# main.net
KiCad netlist of a schematic drawn in Altium Designer
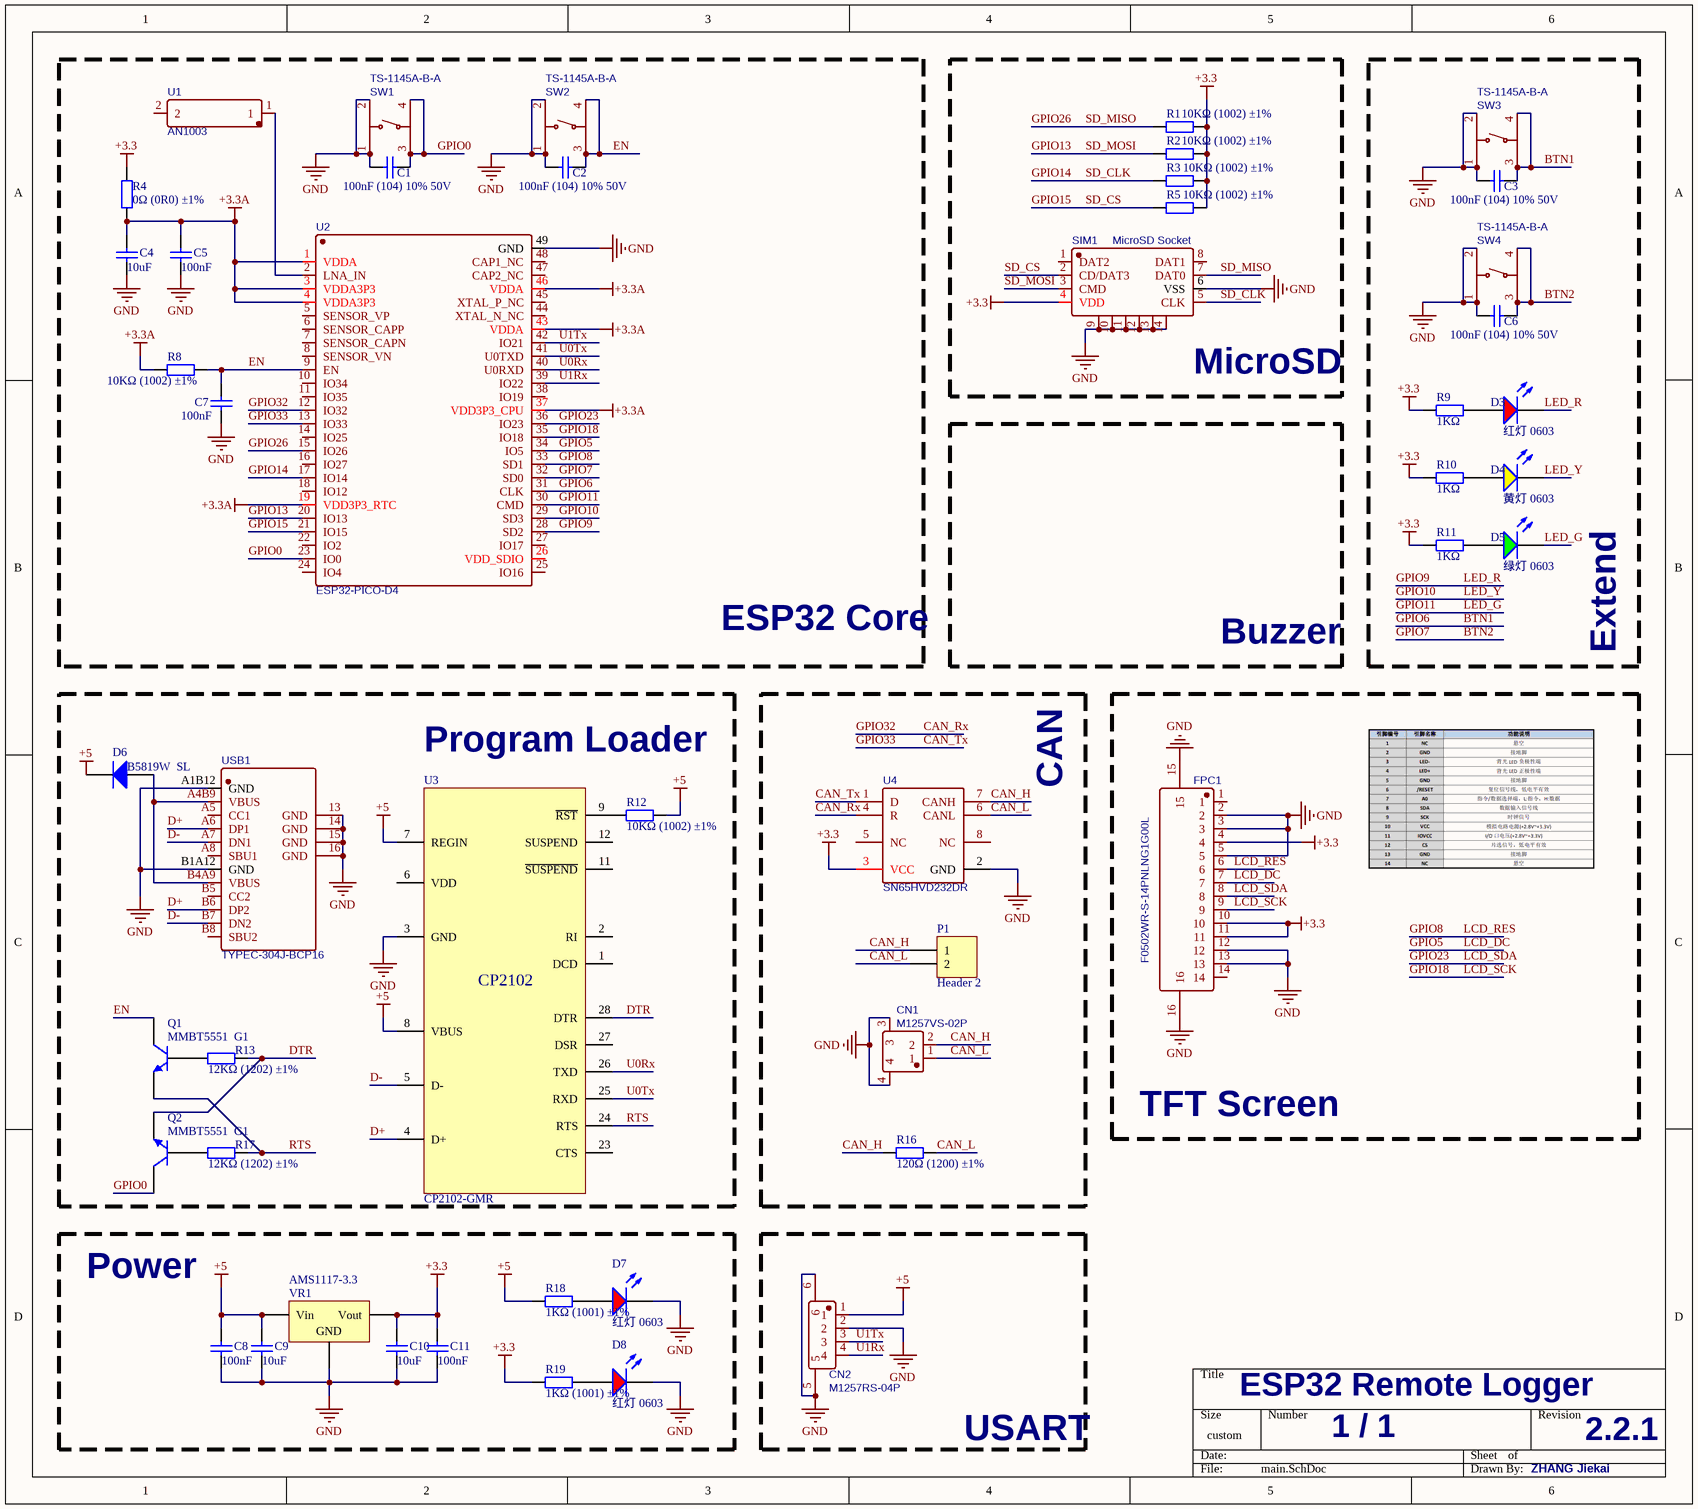
[diagram p0: main.SchDoc]

(export (version "E")
  (design (tool "Eeschema 10.0.6"))
  (components
    (comp (ref "C1")
      (value "100nF (104) 10% 50V")
      (footprint "0603_C")
      (description "贴片电容")
      (libsource (lib "Miscellaneous Devices LC") (part "0603 100nF (104) 10% 50V"))
    )
    (comp (ref "C2")
      (value "100nF (104) 10% 50V")
      (footprint "0603_C")
      (description "贴片电容")
      (libsource (lib "Miscellaneous Devices LC") (part "0603 100nF (104) 10% 50V"))
    )
    (comp (ref "C3")
      (value "100nF (104) 10% 50V")
      (footprint "0603_C")
      (description "贴片电容")
      (libsource (lib "Miscellaneous Devices LC") (part "0603 100nF (104) 10% 50V"))
    )
    (comp (ref "C4")
      (value "10uF")
      (footprint "0603_C")
      (description "贴片电容")
      (libsource (lib "Miscellaneous Devices LC") (part "0603 10uF (106) 10% 10V"))
    )
    (comp (ref "C5")
      (value "100nF")
      (footprint "0603_C")
      (description "贴片电容")
      (libsource (lib "Miscellaneous Devices LC") (part "0603 100nF (104) 10% 50V"))
    )
    (comp (ref "C6")
      (value "100nF (104) 10% 50V")
      (footprint "0603_C")
      (description "贴片电容")
      (libsource (lib "Miscellaneous Devices LC") (part "0603 100nF (104) 10% 50V"))
    )
    (comp (ref "C7")
      (value "100nF")
      (footprint "0603_C")
      (description "贴片电容")
      (libsource (lib "Miscellaneous Devices LC") (part "0603 100nF (104) 10% 50V"))
    )
    (comp (ref "C8")
      (value "100nF")
      (footprint "0603_C")
      (description "贴片电容")
      (libsource (lib "Miscellaneous Devices LC") (part "0603 100nF (104) 10% 50V"))
    )
    (comp (ref "C9")
      (value "10uF")
      (footprint "0603_C")
      (description "贴片电容")
      (libsource (lib "Miscellaneous Devices LC") (part "0603 10uF (106) 10% 10V"))
    )
    (comp (ref "C10")
      (value "10uF")
      (footprint "0603_C")
      (description "贴片电容")
      (libsource (lib "Miscellaneous Devices LC") (part "0603 10uF (106) 10% 10V"))
    )
    (comp (ref "C11")
      (value "100nF")
      (footprint "0603_C")
      (description "贴片电容")
      (libsource (lib "Miscellaneous Devices LC") (part "0603 100nF (104) 10% 50V"))
    )
    (comp (ref "CN1")
      (value "M1257VS-02P")
      (footprint "CONN-SMD_P1.25_M1257VS-02P")
      (fields (field (name "BOM_SUPPLIER PART") "C541819") (field (name "CONTRIBUTOR") "LCSC"))
      (libsource (lib "GH2P_Stand") (part "M1257VS-02P"))
    )
    (comp (ref "CN2")
      (value "M1257RS-04P")
      (footprint "CONN-SMD_M1257RS-04P")
      (fields (field (name "BOM_SUPPLIER PART") "C541828") (field (name "CONTRIBUTOR") "LCSC"))
      (libsource (lib "GH-lay-4P") (part "M1257RS-04P"))
    )
    (comp (ref "D3")
      (value "红灯 0603")
      (footprint "0603_LED_S1")
      (description "发光二极管")
      (libsource (lib "Miscellaneous Devices LC") (part "0603 红灯"))
    )
    (comp (ref "D4")
      (value "黄灯 0603")
      (footprint "0603_LED_S1")
      (description "发光二极管")
      (libsource (lib "Miscellaneous Devices LC") (part "0603 黄灯"))
    )
    (comp (ref "D5")
      (value "绿灯 0603")
      (footprint "0603_LED_S1")
      (description "发光二极管")
      (libsource (lib "Miscellaneous Devices LC") (part "0603 绿灯"))
    )
    (comp (ref "D6")
      (value "B5819W  SL")
      (footprint "SOD-123")
      (description "肖特基二极管")
      (libsource (lib "Miscellaneous Devices LC") (part "SOD-123 B5819W  SL"))
    )
    (comp (ref "D7")
      (value "红灯 0603")
      (footprint "0603_LED_S1")
      (description "发光二极管")
      (libsource (lib "Miscellaneous Devices LC") (part "0603 红灯"))
    )
    (comp (ref "D8")
      (value "红灯 0603")
      (footprint "0603_LED_S1")
      (description "发光二极管")
      (libsource (lib "Miscellaneous Devices LC") (part "0603 红灯"))
    )
    (comp (ref "FPC1")
      (value "F0502WR-S-14PNLNG1G00L")
      (footprint "FPC-SMD_P0.50-14P_F0500WR-S")
      (fields (field (name "BOM_SUPPLIER PART") "C247902") (field (name "CONTRIBUTOR") "LCSC"))
      (libsource (lib "14P-FFC-Connector") (part "F0502WR-S-14PNLNG1G00L"))
    )
    (comp (ref "P1")
      (value "Header 2")
      (footprint "HDR1X2")
      (description "Header, 2-Pin")
      (fields (field (name "PUBLISHER") "Altium Limited"))
      (libsource (lib "Miscellaneous Connectors") (part "Header 2"))
    )
    (comp (ref "Q1")
      (value "MMBT5551  G1")
      (footprint "SOT-23(SOT-23-3)")
      (description "三极管")
      (libsource (lib "Miscellaneous Devices LC") (part "SOT-23 MMBT5551  G1"))
    )
    (comp (ref "Q2")
      (value "MMBT5551  G1")
      (footprint "SOT-23(SOT-23-3)")
      (description "三极管")
      (libsource (lib "Miscellaneous Devices LC") (part "SOT-23 MMBT5551  G1"))
    )
    (comp (ref "R1")
      (value "10KΩ (1002) ±1%")
      (footprint "0603_R")
      (description "贴片电阻")
      (libsource (lib "Miscellaneous Devices LC") (part "0603 10KΩ (1002) 1%"))
    )
    (comp (ref "R2")
      (value "10KΩ (1002) ±1%")
      (footprint "0603_R")
      (description "贴片电阻")
      (libsource (lib "Miscellaneous Devices LC") (part "0603 10KΩ (1002) 1%"))
    )
    (comp (ref "R3")
      (value "10KΩ (1002) ±1%")
      (footprint "0603_R")
      (description "贴片电阻")
      (libsource (lib "Miscellaneous Devices LC") (part "0603 10KΩ (1002) 1%"))
    )
    (comp (ref "R4")
      (value "0Ω (0R0) ±1%")
      (footprint "0603_R")
      (description "贴片电阻")
      (libsource (lib "Miscellaneous Devices LC") (part "0603 0Ω (0R0) 1%"))
    )
    (comp (ref "R5")
      (value "10KΩ (1002) ±1%")
      (footprint "0603_R")
      (description "贴片电阻")
      (libsource (lib "Miscellaneous Devices LC") (part "0603 10KΩ (1002) 1%"))
    )
    (comp (ref "R8")
      (value "10KΩ (1002) ±1%")
      (footprint "0603_R")
      (description "贴片电阻")
      (libsource (lib "Miscellaneous Devices LC") (part "0603 10KΩ (1002) 1%"))
    )
    (comp (ref "R9")
      (value "1KΩ")
      (footprint "0603_R")
      (description "贴片电阻")
      (libsource (lib "") (part "0603 1KΩ (1001) 1%_1"))
    )
    (comp (ref "R10")
      (value "1KΩ")
      (footprint "0603_R")
      (description "贴片电阻")
      (libsource (lib "") (part "0603 1KΩ (1001) 1%_1"))
    )
    (comp (ref "R11")
      (value "1KΩ")
      (footprint "0603_R")
      (description "贴片电阻")
      (libsource (lib "") (part "0603 1KΩ (1001) 1%_1"))
    )
    (comp (ref "R12")
      (value "10KΩ (1002) ±1%")
      (footprint "0603_R")
      (description "贴片电阻")
      (libsource (lib "Miscellaneous Devices LC") (part "0603 10KΩ (1002) 1%"))
    )
    (comp (ref "R13")
      (value "12KΩ (1202) ±1%")
      (footprint "0603_R")
      (description "贴片电阻")
      (libsource (lib "Miscellaneous Devices LC") (part "0603 12KΩ (1202) 1%"))
    )
    (comp (ref "R16")
      (value "120Ω (1200) ±1%")
      (footprint "0603_R")
      (description "贴片电阻")
      (libsource (lib "Miscellaneous Devices LC") (part "0603 120Ω (1200) 1%"))
    )
    (comp (ref "R17")
      (value "12KΩ (1202) ±1%")
      (footprint "0603_R")
      (description "贴片电阻")
      (libsource (lib "Miscellaneous Devices LC") (part "0603 12KΩ (1202) 1%"))
    )
    (comp (ref "R18")
      (value "1KΩ (1001) ±1%")
      (footprint "0603_R")
      (description "贴片电阻")
      (libsource (lib "Miscellaneous Devices LC") (part "0603 1KΩ (1001) 1%"))
    )
    (comp (ref "R19")
      (value "1KΩ (1001) ±1%")
      (footprint "0603_R")
      (description "贴片电阻")
      (libsource (lib "Miscellaneous Devices LC") (part "0603 1KΩ (1001) 1%"))
    )
    (comp (ref "SIM1")
      (value "MicroSD Socket")
      (footprint "SIM-SMD_8P-1040310811")
      (fields
        (field (name "BOM_SUPPLIER PART") "C585350")
        (field (name "BOM_MANUFACTURER PART") "1040310811")
        (field (name "CONTRIBUTOR") "LCSC")
      )
      (libsource (lib "MicroSD-Socket") (part "1040310811"))
    )
    (comp (ref "SW1")
      (value "TS-1145A-B-A")
      (footprint "SW-SMD_4P-L4.2-W3.2-P2.15-LS5.2")
      (fields (field (name "BOM_SUPPLIER PART") "C318904") (field (name "CONTRIBUTOR") "LCSC"))
      (libsource (lib "Pad-Button") (part "TS-1145A-B-A"))
    )
    (comp (ref "SW2")
      (value "TS-1145A-B-A")
      (footprint "SW-SMD_4P-L4.2-W3.2-P2.15-LS5.2")
      (fields (field (name "BOM_SUPPLIER PART") "C318904") (field (name "CONTRIBUTOR") "LCSC"))
      (libsource (lib "Pad-Button") (part "TS-1145A-B-A"))
    )
    (comp (ref "SW3")
      (value "TS-1145A-B-A")
      (footprint "SW-SMD_4P-L4.2-W3.2-P2.15-LS5.2")
      (fields (field (name "BOM_SUPPLIER PART") "C318904") (field (name "CONTRIBUTOR") "LCSC"))
      (libsource (lib "Pad-Button") (part "TS-1145A-B-A"))
    )
    (comp (ref "SW4")
      (value "TS-1145A-B-A")
      (footprint "SW-SMD_4P-L4.2-W3.2-P2.15-LS5.2")
      (fields (field (name "BOM_SUPPLIER PART") "C318904") (field (name "CONTRIBUTOR") "LCSC"))
      (libsource (lib "Pad-Button") (part "TS-1145A-B-A"))
    )
    (comp (ref "U1")
      (value "AN1003")
      (footprint "ANT-SMD_L10.3-W3.0")
      (fields (field (name "BOM_SUPPLIER PART") "C239240") (field (name "CONTRIBUTOR") "LCSC"))
      (libsource (lib "AN1003") (part "AN1003"))
    )
    (comp (ref "U2")
      (value "ESP32-PICO-D4")
      (footprint "QFN-48_L7.0-W7.0-P0.50-BL-EP5.4")
      (fields (field (name "BOM_SUPPLIER PART") "C193707") (field (name "CONTRIBUTOR") "LCSC"))
      (libsource (lib "ESP32-PICO-D4") (part "ESP32-PICO-D4"))
    )
    (comp (ref "U3")
      (value "CP2102-GMR")
      (footprint "QFN-28_5x5x05P")
      (description "USB")
      (libsource (lib "Miscellaneous Devices LC") (part "CP2102-GMR_[C6568]"))
    )
    (comp (ref "U4")
      (value "SN65HVD232DR")
      (footprint "SOIC-8_L5.0-W4.0-P1.27-LS6.0-BL")
      (fields (field (name "BOM_SUPPLIER PART") "C30530"))
      (libsource (lib "SN65HVD232DR") (part "SN65HVD232DR"))
    )
    (comp (ref "USB1")
      (value "TYPEC-304J-BCP16")
      (footprint "USB-C-SMD_TYPEC-304J-BCP16")
      (fields (field (name "BOM_SUPPLIER PART") "C2835315") (field (name "CONTRIBUTOR") "LCSC"))
      (libsource (lib "Pad-Typec") (part "TYPEC-304J-BCP16"))
    )
    (comp (ref "VR1")
      (value "AMS1117-3.3")
      (footprint "SOT-223")
      (description "低压差线性稳压(LDO)")
      (libsource (lib "Miscellaneous Devices LC") (part "SOT-223 AMS1117-3.3"))
    )
  )
  (nets
    (net (code "1") (name "+3.3") (class "Default")
      (node (ref "C10") (pin "2") (pinfunction "2_2") (pintype "passive"))
      (node (ref "C11") (pin "2") (pinfunction "2_2") (pintype "passive"))
      (node (ref "FPC1") (pin "10") (pinfunction "10_10") (pintype "passive"))
      (node (ref "FPC1") (pin "11") (pinfunction "11_11") (pintype "passive"))
      (node (ref "FPC1") (pin "4") (pinfunction "4_4") (pintype "passive"))
      (node (ref "R1") (pin "2") (pinfunction "2_2") (pintype "passive"))
      (node (ref "R10") (pin "2") (pinfunction "2_2") (pintype "passive"))
      (node (ref "R11") (pin "2") (pinfunction "2_2") (pintype "passive"))
      (node (ref "R19") (pin "1") (pinfunction "1_1") (pintype "passive"))
      (node (ref "R2") (pin "2") (pinfunction "2_2") (pintype "passive"))
      (node (ref "R3") (pin "2") (pinfunction "2_2") (pintype "passive"))
      (node (ref "R4") (pin "2") (pinfunction "2_2") (pintype "passive"))
      (node (ref "R5") (pin "2") (pinfunction "2_2") (pintype "passive"))
      (node (ref "R9") (pin "2") (pinfunction "2_2") (pintype "passive"))
      (node (ref "SIM1") (pin "4") (pinfunction "VDD_4") (pintype "passive"))
      (node (ref "U4") (pin "3") (pinfunction "VCC_3") (pintype "passive"))
      (node (ref "VR1") (pin "2") (pinfunction "Vout_2") (pintype "passive"))
    )
    (net (code "2") (name "+3.3A") (class "Default")
      (node (ref "C4") (pin "2") (pinfunction "2_2") (pintype "passive"))
      (node (ref "C5") (pin "2") (pinfunction "2_2") (pintype "passive"))
      (node (ref "R4") (pin "1") (pinfunction "1_1") (pintype "passive"))
      (node (ref "R8") (pin "1") (pinfunction "1_1") (pintype "passive"))
      (node (ref "U2") (pin "1") (pinfunction "VDDA_1") (pintype "passive"))
      (node (ref "U2") (pin "19") (pinfunction "VDD3P3_RTC_19") (pintype "passive"))
      (node (ref "U2") (pin "3") (pinfunction "VDDA3P3_3") (pintype "passive"))
      (node (ref "U2") (pin "37") (pinfunction "VDD3P3_CPU_37") (pintype "passive"))
      (node (ref "U2") (pin "4") (pinfunction "VDDA3P3_4") (pintype "passive"))
      (node (ref "U2") (pin "43") (pinfunction "VDDA_43") (pintype "passive"))
      (node (ref "U2") (pin "46") (pinfunction "VDDA_46") (pintype "passive"))
    )
    (net (code "3") (name "+5") (class "Default")
      (node (ref "C8") (pin "2") (pinfunction "2_2") (pintype "passive"))
      (node (ref "C9") (pin "2") (pinfunction "2_2") (pintype "passive"))
      (node (ref "CN2") (pin "1") (pinfunction "1_1") (pintype "passive"))
      (node (ref "D6") (pin "2") (pinfunction "K_2") (pintype "passive"))
      (node (ref "R12") (pin "2") (pinfunction "2_2") (pintype "passive"))
      (node (ref "R18") (pin "1") (pinfunction "1_1") (pintype "passive"))
      (node (ref "U3") (pin "7") (pinfunction "REGIN_7") (pintype "passive"))
      (node (ref "U3") (pin "8") (pinfunction "VBUS_8") (pintype "passive"))
      (node (ref "VR1") (pin "3") (pinfunction "Vin_3") (pintype "passive"))
    )
    (net (code "4") (name "/BTN1") (class "Default")
      (node (ref "C3") (pin "2") (pinfunction "2_2") (pintype "passive"))
      (node (ref "SW3") (pin "3") (pinfunction "3_3") (pintype "passive"))
      (node (ref "SW3") (pin "4") (pinfunction "4_4") (pintype "passive"))
      (node (ref "U2") (pin "31") (pinfunction "CLK_31") (pintype "passive"))
    )
    (net (code "5") (name "/BTN2") (class "Default")
      (node (ref "C6") (pin "2") (pinfunction "2_2") (pintype "passive"))
      (node (ref "SW4") (pin "3") (pinfunction "3_3") (pintype "passive"))
      (node (ref "SW4") (pin "4") (pinfunction "4_4") (pintype "passive"))
      (node (ref "U2") (pin "32") (pinfunction "SD0_32") (pintype "passive"))
    )
    (net (code "6") (name "/CAN_H") (class "Default")
      (node (ref "CN1") (pin "2") (pinfunction "2_2") (pintype "passive"))
      (node (ref "P1") (pin "1") (pinfunction "1_1") (pintype "passive"))
      (node (ref "R16") (pin "1") (pinfunction "1_1") (pintype "passive"))
      (node (ref "U4") (pin "7") (pinfunction "CANH_7") (pintype "passive"))
    )
    (net (code "7") (name "/CAN_L") (class "Default")
      (node (ref "CN1") (pin "1") (pinfunction "1_1") (pintype "passive"))
      (node (ref "P1") (pin "2") (pinfunction "2_2") (pintype "passive"))
      (node (ref "R16") (pin "2") (pinfunction "2_2") (pintype "passive"))
      (node (ref "U4") (pin "6") (pinfunction "CANL_6") (pintype "passive"))
    )
    (net (code "8") (name "/CAN_Rx") (class "Default")
      (node (ref "U2") (pin "12") (pinfunction "IO32_12") (pintype "passive"))
      (node (ref "U4") (pin "4") (pinfunction "R_4") (pintype "passive"))
    )
    (net (code "9") (name "/CAN_Tx") (class "Default")
      (node (ref "U2") (pin "13") (pinfunction "IO33_13") (pintype "passive"))
      (node (ref "U4") (pin "1") (pinfunction "D_1") (pintype "passive"))
    )
    (net (code "10") (name "/D+") (class "Default")
      (node (ref "U3") (pin "4") (pinfunction "D+_4") (pintype "passive"))
      (node (ref "USB1") (pin "A6") (pinfunction "DP1_A6") (pintype "passive"))
      (node (ref "USB1") (pin "B6") (pinfunction "DP2_B6") (pintype "passive"))
    )
    (net (code "11") (name "/D-") (class "Default")
      (node (ref "U3") (pin "5") (pinfunction "D-_5") (pintype "passive"))
      (node (ref "USB1") (pin "A7") (pinfunction "DN1_A7") (pintype "passive"))
      (node (ref "USB1") (pin "B7") (pinfunction "DN2_B7") (pintype "passive"))
    )
    (net (code "12") (name "/DTR") (class "Default")
      (node (ref "Q2") (pin "2") (pinfunction "E_2") (pintype "passive"))
      (node (ref "R13") (pin "2") (pinfunction "2_2") (pintype "passive"))
      (node (ref "U3") (pin "28") (pinfunction "DTR_28") (pintype "passive"))
    )
    (net (code "13") (name "/EN") (class "Default")
      (node (ref "C2") (pin "2") (pinfunction "2_2") (pintype "passive"))
      (node (ref "C7") (pin "2") (pinfunction "2_2") (pintype "passive"))
      (node (ref "Q1") (pin "3") (pinfunction "C_3") (pintype "passive"))
      (node (ref "R8") (pin "2") (pinfunction "2_2") (pintype "passive"))
      (node (ref "SW2") (pin "3") (pinfunction "3_3") (pintype "passive"))
      (node (ref "SW2") (pin "4") (pinfunction "4_4") (pintype "passive"))
      (node (ref "U2") (pin "9") (pinfunction "EN_9") (pintype "passive"))
    )
    (net (code "14") (name "/GPIO0") (class "Default")
      (node (ref "C1") (pin "2") (pinfunction "2_2") (pintype "passive"))
      (node (ref "Q2") (pin "3") (pinfunction "C_3") (pintype "passive"))
      (node (ref "SW1") (pin "3") (pinfunction "3_3") (pintype "passive"))
      (node (ref "SW1") (pin "4") (pinfunction "4_4") (pintype "passive"))
      (node (ref "U2") (pin "23") (pinfunction "IO0_23") (pintype "passive"))
    )
    (net (code "15") (name "/GPIO5") (class "Default")
      (node (ref "FPC1") (pin "7") (pinfunction "7_7") (pintype "passive"))
      (node (ref "U2") (pin "34") (pinfunction "IO5_34") (pintype "passive"))
    )
    (net (code "16") (name "/GPIO8") (class "Default")
      (node (ref "FPC1") (pin "6") (pinfunction "6_6") (pintype "passive"))
      (node (ref "U2") (pin "33") (pinfunction "SD1_33") (pintype "passive"))
    )
    (net (code "17") (name "/GPIO9") (class "Default")
      (node (ref "D3") (pin "K") (pinfunction "K_K") (pintype "passive"))
      (node (ref "U2") (pin "28") (pinfunction "SD2_28") (pintype "passive"))
    )
    (net (code "18") (name "/GPIO10") (class "Default")
      (node (ref "D4") (pin "K") (pinfunction "K_K") (pintype "passive"))
      (node (ref "U2") (pin "29") (pinfunction "SD3_29") (pintype "passive"))
    )
    (net (code "19") (name "/GPIO11") (class "Default")
      (node (ref "D5") (pin "K") (pinfunction "K_K") (pintype "passive"))
      (node (ref "U2") (pin "30") (pinfunction "CMD_30") (pintype "passive"))
    )
    (net (code "20") (name "/GPIO13") (class "Default")
      (node (ref "R2") (pin "1") (pinfunction "1_1") (pintype "passive"))
      (node (ref "SIM1") (pin "3") (pinfunction "CMD_3") (pintype "passive"))
      (node (ref "U2") (pin "20") (pinfunction "IO13_20") (pintype "passive"))
    )
    (net (code "21") (name "/GPIO14") (class "Default")
      (node (ref "R3") (pin "1") (pinfunction "1_1") (pintype "passive"))
      (node (ref "SIM1") (pin "5") (pinfunction "CLK_5") (pintype "passive"))
      (node (ref "U2") (pin "17") (pinfunction "IO14_17") (pintype "passive"))
    )
    (net (code "22") (name "/GPIO15") (class "Default")
      (node (ref "R5") (pin "1") (pinfunction "1_1") (pintype "passive"))
      (node (ref "SIM1") (pin "2") (pinfunction "CD/DAT3_2") (pintype "passive"))
      (node (ref "U2") (pin "21") (pinfunction "IO15_21") (pintype "passive"))
    )
    (net (code "23") (name "/GPIO18") (class "Default")
      (node (ref "FPC1") (pin "9") (pinfunction "9_9") (pintype "passive"))
      (node (ref "U2") (pin "35") (pinfunction "IO18_35") (pintype "passive"))
    )
    (net (code "24") (name "/GPIO23") (class "Default")
      (node (ref "FPC1") (pin "8") (pinfunction "8_8") (pintype "passive"))
      (node (ref "U2") (pin "36") (pinfunction "IO23_36") (pintype "passive"))
    )
    (net (code "25") (name "/GPIO26") (class "Default")
      (node (ref "R1") (pin "1") (pinfunction "1_1") (pintype "passive"))
      (node (ref "SIM1") (pin "7") (pinfunction "DAT0_7") (pintype "passive"))
      (node (ref "U2") (pin "15") (pinfunction "IO26_15") (pintype "passive"))
    )
    (net (code "26") (name "/RTS") (class "Default")
      (node (ref "Q1") (pin "2") (pinfunction "E_2") (pintype "passive"))
      (node (ref "R17") (pin "2") (pinfunction "2_2") (pintype "passive"))
      (node (ref "U3") (pin "24") (pinfunction "RTS_24") (pintype "passive"))
    )
    (net (code "27") (name "/U0Rx") (class "Default")
      (node (ref "U2") (pin "40") (pinfunction "U0RXD_40") (pintype "passive"))
      (node (ref "U3") (pin "26") (pinfunction "TXD_26") (pintype "passive"))
    )
    (net (code "28") (name "/U0Tx") (class "Default")
      (node (ref "U2") (pin "41") (pinfunction "U0TXD_41") (pintype "passive"))
      (node (ref "U3") (pin "25") (pinfunction "RXD_25") (pintype "passive"))
    )
    (net (code "29") (name "/U1Rx") (class "Default")
      (node (ref "CN2") (pin "4") (pinfunction "4_4") (pintype "passive"))
      (node (ref "U2") (pin "39") (pinfunction "IO22_39") (pintype "passive"))
    )
    (net (code "30") (name "/U1Tx") (class "Default")
      (node (ref "CN2") (pin "3") (pinfunction "3_3") (pintype "passive"))
      (node (ref "U2") (pin "42") (pinfunction "IO21_42") (pintype "passive"))
    )
    (net (code "31") (name "GND") (class "Default")
      (node (ref "C1") (pin "1") (pinfunction "1_1") (pintype "passive"))
      (node (ref "C10") (pin "1") (pinfunction "1_1") (pintype "passive"))
      (node (ref "C11") (pin "1") (pinfunction "1_1") (pintype "passive"))
      (node (ref "C2") (pin "1") (pinfunction "1_1") (pintype "passive"))
      (node (ref "C3") (pin "1") (pinfunction "1_1") (pintype "passive"))
      (node (ref "C4") (pin "1") (pinfunction "1_1") (pintype "passive"))
      (node (ref "C5") (pin "1") (pinfunction "1_1") (pintype "passive"))
      (node (ref "C6") (pin "1") (pinfunction "1_1") (pintype "passive"))
      (node (ref "C7") (pin "1") (pinfunction "1_1") (pintype "passive"))
      (node (ref "C8") (pin "1") (pinfunction "1_1") (pintype "passive"))
      (node (ref "C9") (pin "1") (pinfunction "1_1") (pintype "passive"))
      (node (ref "CN1") (pin "3") (pinfunction "3_3") (pintype "passive"))
      (node (ref "CN1") (pin "4") (pinfunction "4_4") (pintype "passive"))
      (node (ref "CN2") (pin "2") (pinfunction "2_2") (pintype "passive"))
      (node (ref "CN2") (pin "5") (pinfunction "5_5") (pintype "passive"))
      (node (ref "CN2") (pin "6") (pinfunction "6_6") (pintype "passive"))
      (node (ref "D7") (pin "K") (pinfunction "K_K") (pintype "passive"))
      (node (ref "D8") (pin "K") (pinfunction "K_K") (pintype "passive"))
      (node (ref "FPC1") (pin "12") (pinfunction "12_12") (pintype "passive"))
      (node (ref "FPC1") (pin "13") (pinfunction "13_13") (pintype "passive"))
      (node (ref "FPC1") (pin "15") (pinfunction "15_15") (pintype "passive"))
      (node (ref "FPC1") (pin "16") (pinfunction "16_16") (pintype "passive"))
      (node (ref "FPC1") (pin "2") (pinfunction "2_2") (pintype "passive"))
      (node (ref "FPC1") (pin "3") (pinfunction "3_3") (pintype "passive"))
      (node (ref "FPC1") (pin "5") (pinfunction "5_5") (pintype "passive"))
      (node (ref "SIM1") (pin "10") (pinfunction "10_10") (pintype "passive"))
      (node (ref "SIM1") (pin "11") (pinfunction "11_11") (pintype "passive"))
      (node (ref "SIM1") (pin "12") (pinfunction "12_12") (pintype "passive"))
      (node (ref "SIM1") (pin "13") (pinfunction "13_13") (pintype "passive"))
      (node (ref "SIM1") (pin "14") (pinfunction "14_14") (pintype "passive"))
      (node (ref "SIM1") (pin "6") (pinfunction "VSS_6") (pintype "passive"))
      (node (ref "SIM1") (pin "9") (pinfunction "9_9") (pintype "passive"))
      (node (ref "SW1") (pin "1") (pinfunction "1_1") (pintype "passive"))
      (node (ref "SW1") (pin "2") (pinfunction "2_2") (pintype "passive"))
      (node (ref "SW2") (pin "1") (pinfunction "1_1") (pintype "passive"))
      (node (ref "SW2") (pin "2") (pinfunction "2_2") (pintype "passive"))
      (node (ref "SW3") (pin "1") (pinfunction "1_1") (pintype "passive"))
      (node (ref "SW3") (pin "2") (pinfunction "2_2") (pintype "passive"))
      (node (ref "SW4") (pin "1") (pinfunction "1_1") (pintype "passive"))
      (node (ref "SW4") (pin "2") (pinfunction "2_2") (pintype "passive"))
      (node (ref "U2") (pin "49") (pinfunction "GND_49") (pintype "passive"))
      (node (ref "U3") (pin "3") (pinfunction "GND_3") (pintype "passive"))
      (node (ref "U4") (pin "2") (pinfunction "GND_2") (pintype "passive"))
      (node (ref "USB1") (pin "13") (pinfunction "GND_13") (pintype "passive"))
      (node (ref "USB1") (pin "14") (pinfunction "GND_14") (pintype "passive"))
      (node (ref "USB1") (pin "15") (pinfunction "GND_15") (pintype "passive"))
      (node (ref "USB1") (pin "16") (pinfunction "GND_16") (pintype "passive"))
      (node (ref "USB1") (pin "A1B12") (pinfunction "GND_A1B12") (pintype "passive"))
      (node (ref "USB1") (pin "B1A12") (pinfunction "GND_B1A12") (pintype "passive"))
      (node (ref "VR1") (pin "1") (pinfunction "GND_1") (pintype "passive"))
    )
    (net (code "32") (name "Net-(D3-PadA)") (class "Default")
      (node (ref "D3") (pin "A") (pinfunction "A_A") (pintype "passive"))
      (node (ref "R9") (pin "1") (pinfunction "1_1") (pintype "passive"))
    )
    (net (code "33") (name "Net-(D4-PadA)") (class "Default")
      (node (ref "D4") (pin "A") (pinfunction "A_A") (pintype "passive"))
      (node (ref "R10") (pin "1") (pinfunction "1_1") (pintype "passive"))
    )
    (net (code "34") (name "Net-(D5-PadA)") (class "Default")
      (node (ref "D5") (pin "A") (pinfunction "A_A") (pintype "passive"))
      (node (ref "R11") (pin "1") (pinfunction "1_1") (pintype "passive"))
    )
    (net (code "35") (name "Net-(D6-A)") (class "Default")
      (node (ref "D6") (pin "1") (pinfunction "A_1") (pintype "passive"))
      (node (ref "USB1") (pin "A4B9") (pinfunction "VBUS_A4B9") (pintype "passive"))
      (node (ref "USB1") (pin "B4A9") (pinfunction "VBUS_B4A9") (pintype "passive"))
    )
    (net (code "36") (name "Net-(D7-PadA)") (class "Default")
      (node (ref "D7") (pin "A") (pinfunction "A_A") (pintype "passive"))
      (node (ref "R18") (pin "2") (pinfunction "2_2") (pintype "passive"))
    )
    (net (code "37") (name "Net-(D8-PadA)") (class "Default")
      (node (ref "D8") (pin "A") (pinfunction "A_A") (pintype "passive"))
      (node (ref "R19") (pin "2") (pinfunction "2_2") (pintype "passive"))
    )
    (net (code "38") (name "Net-(Q1-B)") (class "Default")
      (node (ref "Q1") (pin "1") (pinfunction "B_1") (pintype "passive"))
      (node (ref "R13") (pin "1") (pinfunction "1_1") (pintype "passive"))
    )
    (net (code "39") (name "Net-(Q2-B)") (class "Default")
      (node (ref "Q2") (pin "1") (pinfunction "B_1") (pintype "passive"))
      (node (ref "R17") (pin "1") (pinfunction "1_1") (pintype "passive"))
    )
    (net (code "40") (name "Net-(U2-LNA_IN)") (class "Default")
      (node (ref "U1") (pin "1") (pinfunction "1_1") (pintype "passive"))
      (node (ref "U2") (pin "2") (pinfunction "LNA_IN_2") (pintype "passive"))
    )
    (net (code "41") (name "Net-(U3-~{RST})") (class "Default")
      (node (ref "R12") (pin "1") (pinfunction "1_1") (pintype "passive"))
      (node (ref "U3") (pin "9") (pinfunction "~{RST}_9") (pintype "passive"))
    )
    (net (code "42") (name "unconnected-(FPC1-Pad1)") (class "Default")
      (node (ref "FPC1") (pin "1") (pinfunction "1_1") (pintype "passive"))
    )
    (net (code "43") (name "unconnected-(FPC1-Pad14)") (class "Default")
      (node (ref "FPC1") (pin "14") (pinfunction "14_14") (pintype "passive"))
    )
    (net (code "44") (name "unconnected-(SIM1-DAT1-Pad8)") (class "Default")
      (node (ref "SIM1") (pin "8") (pinfunction "DAT1_8") (pintype "passive"))
    )
    (net (code "45") (name "unconnected-(SIM1-DAT2-Pad1)") (class "Default")
      (node (ref "SIM1") (pin "1") (pinfunction "DAT2_1") (pintype "passive"))
    )
    (net (code "46") (name "unconnected-(U1-Pad2)") (class "Default")
      (node (ref "U1") (pin "2") (pinfunction "2_2") (pintype "passive"))
    )
    (net (code "47") (name "unconnected-(U2-CAP1_NC-Pad48)") (class "Default")
      (node (ref "U2") (pin "48") (pinfunction "CAP1_NC_48") (pintype "passive"))
    )
    (net (code "48") (name "unconnected-(U2-CAP2_NC-Pad47)") (class "Default")
      (node (ref "U2") (pin "47") (pinfunction "CAP2_NC_47") (pintype "passive"))
    )
    (net (code "49") (name "unconnected-(U2-IO2-Pad22)") (class "Default")
      (node (ref "U2") (pin "22") (pinfunction "IO2_22") (pintype "passive"))
    )
    (net (code "50") (name "unconnected-(U2-IO4-Pad24)") (class "Default")
      (node (ref "U2") (pin "24") (pinfunction "IO4_24") (pintype "passive"))
    )
    (net (code "51") (name "unconnected-(U2-IO12-Pad18)") (class "Default")
      (node (ref "U2") (pin "18") (pinfunction "IO12_18") (pintype "passive"))
    )
    (net (code "52") (name "unconnected-(U2-IO16-Pad25)") (class "Default")
      (node (ref "U2") (pin "25") (pinfunction "IO16_25") (pintype "passive"))
    )
    (net (code "53") (name "unconnected-(U2-IO17-Pad27)") (class "Default")
      (node (ref "U2") (pin "27") (pinfunction "IO17_27") (pintype "passive"))
    )
    (net (code "54") (name "unconnected-(U2-IO19-Pad38)") (class "Default")
      (node (ref "U2") (pin "38") (pinfunction "IO19_38") (pintype "passive"))
    )
    (net (code "55") (name "unconnected-(U2-IO25-Pad14)") (class "Default")
      (node (ref "U2") (pin "14") (pinfunction "IO25_14") (pintype "passive"))
    )
    (net (code "56") (name "unconnected-(U2-IO27-Pad16)") (class "Default")
      (node (ref "U2") (pin "16") (pinfunction "IO27_16") (pintype "passive"))
    )
    (net (code "57") (name "unconnected-(U2-IO34-Pad10)") (class "Default")
      (node (ref "U2") (pin "10") (pinfunction "IO34_10") (pintype "passive"))
    )
    (net (code "58") (name "unconnected-(U2-IO35-Pad11)") (class "Default")
      (node (ref "U2") (pin "11") (pinfunction "IO35_11") (pintype "passive"))
    )
    (net (code "59") (name "unconnected-(U2-SENSOR_CAPN-Pad7)") (class "Default")
      (node (ref "U2") (pin "7") (pinfunction "SENSOR_CAPN_7") (pintype "passive"))
    )
    (net (code "60") (name "unconnected-(U2-SENSOR_CAPP-Pad6)") (class "Default")
      (node (ref "U2") (pin "6") (pinfunction "SENSOR_CAPP_6") (pintype "passive"))
    )
    (net (code "61") (name "unconnected-(U2-SENSOR_VN-Pad8)") (class "Default")
      (node (ref "U2") (pin "8") (pinfunction "SENSOR_VN_8") (pintype "passive"))
    )
    (net (code "62") (name "unconnected-(U2-SENSOR_VP-Pad5)") (class "Default")
      (node (ref "U2") (pin "5") (pinfunction "SENSOR_VP_5") (pintype "passive"))
    )
    (net (code "63") (name "unconnected-(U2-VDD_SDIO-Pad26)") (class "Default")
      (node (ref "U2") (pin "26") (pinfunction "VDD_SDIO_26") (pintype "passive"))
    )
    (net (code "64") (name "unconnected-(U2-XTAL_N_NC-Pad44)") (class "Default")
      (node (ref "U2") (pin "44") (pinfunction "XTAL_N_NC_44") (pintype "passive"))
    )
    (net (code "65") (name "unconnected-(U2-XTAL_P_NC-Pad45)") (class "Default")
      (node (ref "U2") (pin "45") (pinfunction "XTAL_P_NC_45") (pintype "passive"))
    )
    (net (code "66") (name "unconnected-(U3-CTS-Pad23)") (class "Default")
      (node (ref "U3") (pin "23") (pinfunction "CTS_23") (pintype "passive"))
    )
    (net (code "67") (name "unconnected-(U3-DCD-Pad1)") (class "Default")
      (node (ref "U3") (pin "1") (pinfunction "DCD_1") (pintype "passive"))
    )
    (net (code "68") (name "unconnected-(U3-DSR-Pad27)") (class "Default")
      (node (ref "U3") (pin "27") (pinfunction "DSR_27") (pintype "passive"))
    )
    (net (code "69") (name "unconnected-(U3-RI-Pad2)") (class "Default")
      (node (ref "U3") (pin "2") (pinfunction "RI_2") (pintype "passive"))
    )
    (net (code "70") (name "unconnected-(U3-SUSPEND-Pad12)") (class "Default")
      (node (ref "U3") (pin "12") (pinfunction "SUSPEND_12") (pintype "passive"))
    )
    (net (code "71") (name "unconnected-(U3-VDD-Pad6)") (class "Default")
      (node (ref "U3") (pin "6") (pinfunction "VDD_6") (pintype "passive"))
    )
    (net (code "72") (name "unconnected-(U3-~{SUSPEND}-Pad11)") (class "Default")
      (node (ref "U3") (pin "11") (pinfunction "~{SUSPEND}_11") (pintype "passive"))
    )
    (net (code "73") (name "unconnected-(U4-NC-Pad5)") (class "Default")
      (node (ref "U4") (pin "5") (pinfunction "NC_5") (pintype "passive"))
    )
    (net (code "74") (name "unconnected-(U4-NC-Pad8)") (class "Default")
      (node (ref "U4") (pin "8") (pinfunction "NC_8") (pintype "passive"))
    )
    (net (code "75") (name "unconnected-(USB1-CC1-PadA5)") (class "Default")
      (node (ref "USB1") (pin "A5") (pinfunction "CC1_A5") (pintype "passive"))
    )
    (net (code "76") (name "unconnected-(USB1-CC2-PadB5)") (class "Default")
      (node (ref "USB1") (pin "B5") (pinfunction "CC2_B5") (pintype "passive"))
    )
    (net (code "77") (name "unconnected-(USB1-SBU1-PadA8)") (class "Default")
      (node (ref "USB1") (pin "A8") (pinfunction "SBU1_A8") (pintype "passive"))
    )
    (net (code "78") (name "unconnected-(USB1-SBU2-PadB8)") (class "Default")
      (node (ref "USB1") (pin "B8") (pinfunction "SBU2_B8") (pintype "passive"))
    )
  )
)
